# PCB-111000_V2.net
KiCad netlist of a schematic drawn in EAGLE
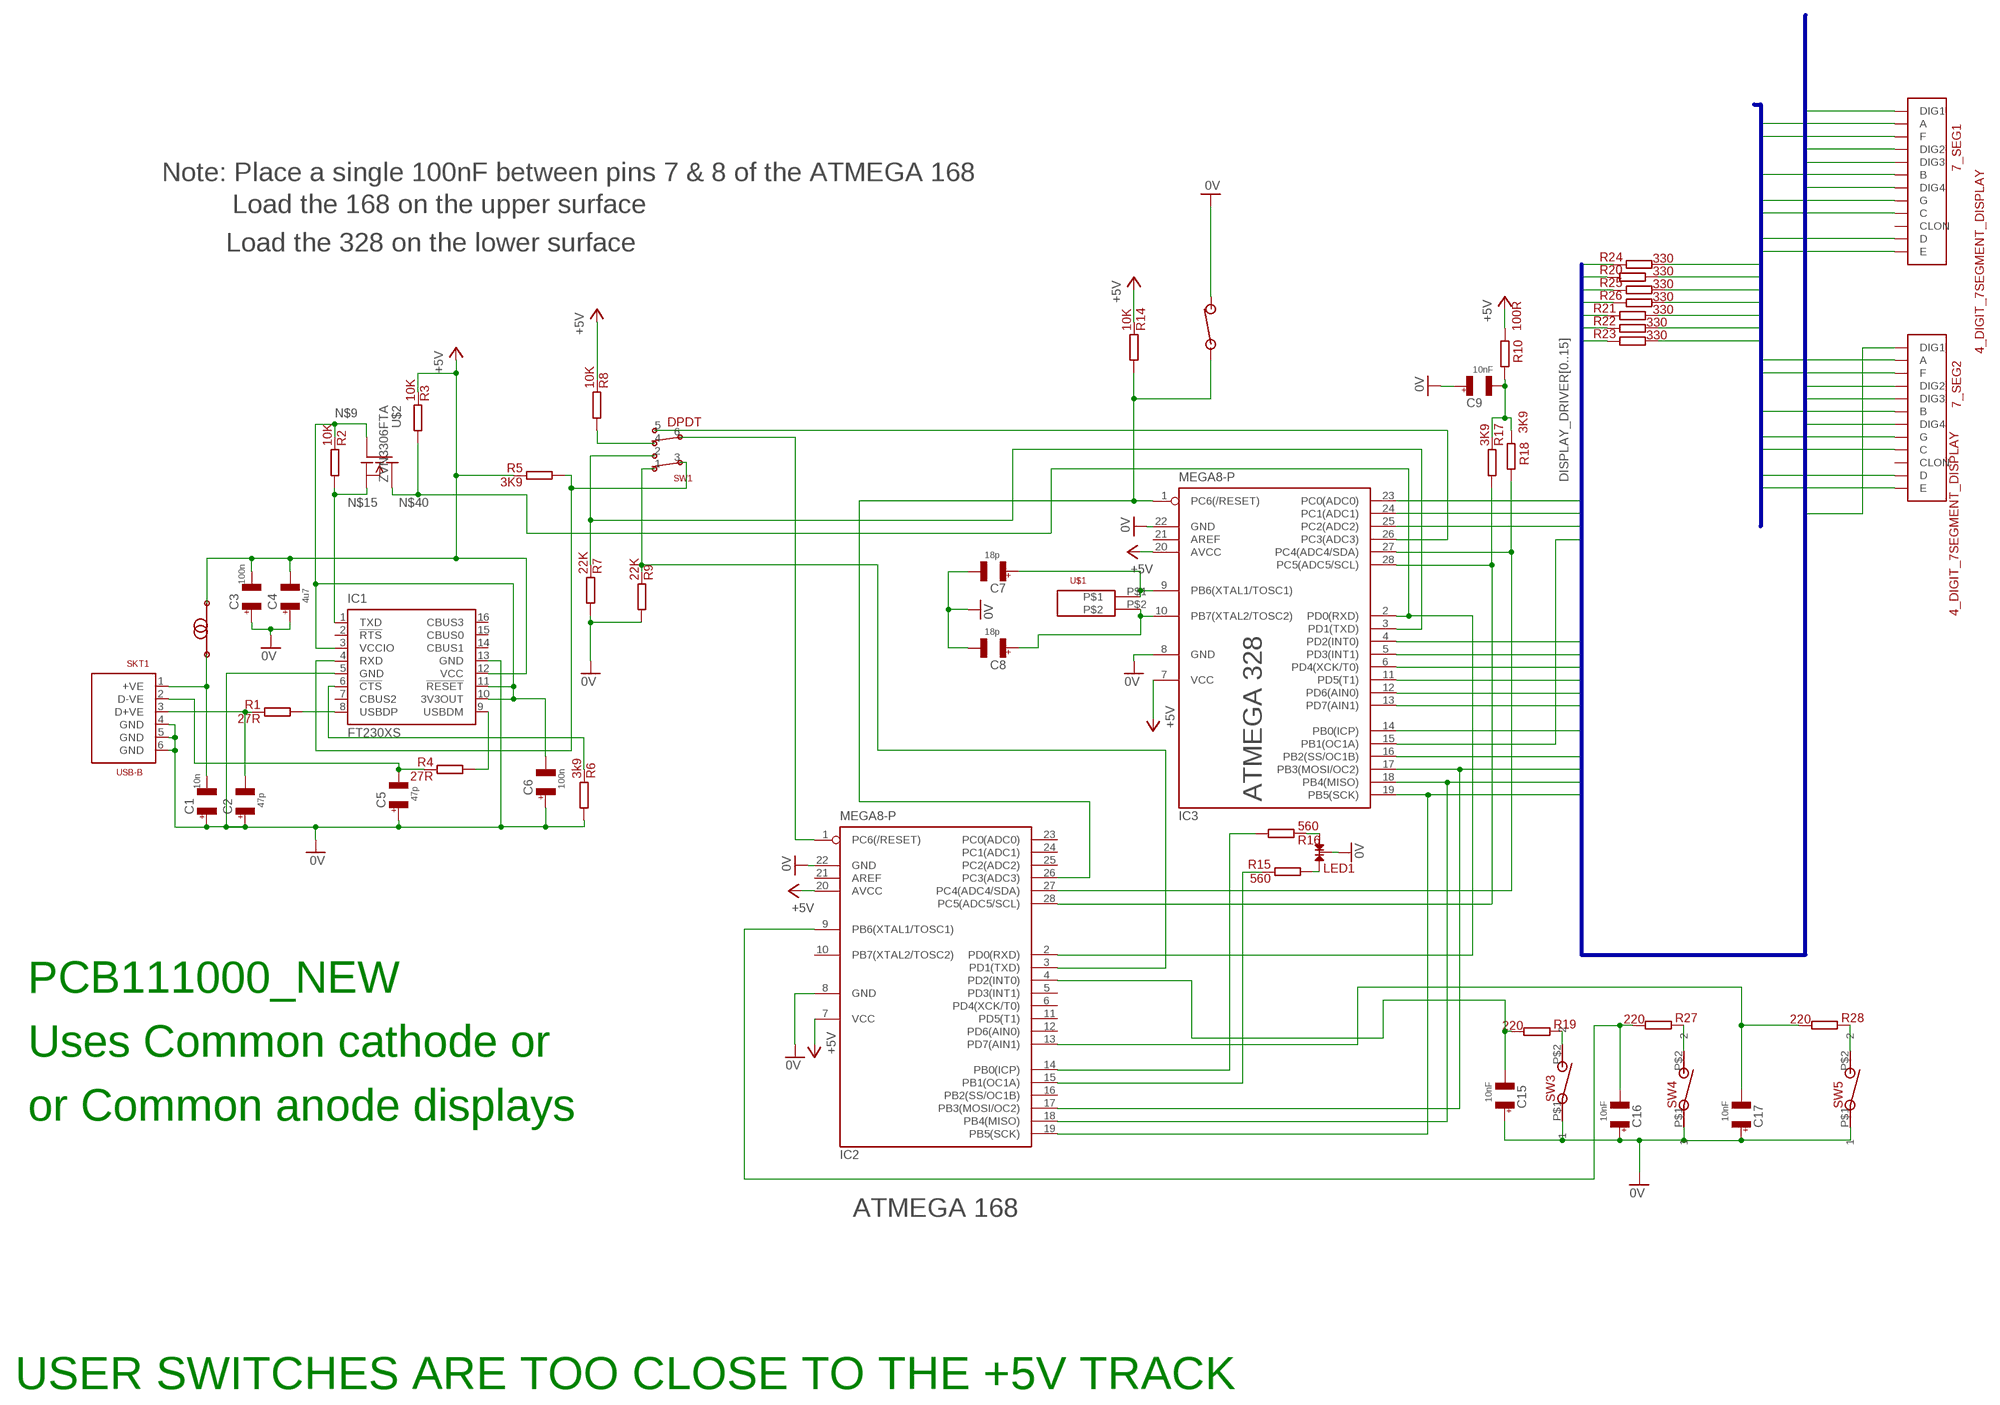
[diagram p0: schematic, sheet 1]

(export (version "E")
  (design (tool "Eeschema 10.0.6"))
  (components
    (comp (ref "7_SEG1")
      (value "4_DIGIT_7SEGMENT_DISPLAY")
      (footprint "eagle-import:4_DIGIT_7SEGMENT_DISPLAY")
      (libsource (lib "eagle-import") (part "4_DIGIT_7SEGMENT_DISPLAY"))
    )
    (comp (ref "7_SEG2")
      (value "4_DIGIT_7SEGMENT_DISPLAY")
      (footprint "eagle-import:4_DIGIT_7SEGMENT_DISPLAY")
      (libsource (lib "eagle-import") (part "4_DIGIT_7SEGMENT_DISPLAY"))
    )
    (comp (ref "C1")
      (value "10n")
      (footprint "eagle-import:1206")
      (libsource (lib "eagle-import") (part "1206C"))
    )
    (comp (ref "C2")
      (value "47p")
      (footprint "eagle-import:1206")
      (libsource (lib "eagle-import") (part "1206C"))
    )
    (comp (ref "C3")
      (value "100n")
      (footprint "eagle-import:1206")
      (libsource (lib "eagle-import") (part "1206C"))
    )
    (comp (ref "C4")
      (value "4u7")
      (footprint "eagle-import:1206")
      (libsource (lib "eagle-import") (part "1206C"))
    )
    (comp (ref "C5")
      (value "47p")
      (footprint "eagle-import:1206")
      (libsource (lib "eagle-import") (part "1206C"))
    )
    (comp (ref "C6")
      (value "100n")
      (footprint "eagle-import:1206")
      (libsource (lib "eagle-import") (part "1206C"))
    )
    (comp (ref "C7")
      (value "18p")
      (footprint "eagle-import:0805")
      (libsource (lib "eagle-import") (part "0805C"))
    )
    (comp (ref "C8")
      (value "18p")
      (footprint "eagle-import:0805")
      (libsource (lib "eagle-import") (part "0805C"))
    )
    (comp (ref "C9")
      (value "10nF")
      (footprint "eagle-import:1206")
      (libsource (lib "eagle-import") (part "1206C"))
    )
    (comp (ref "C15")
      (value "10nF")
      (footprint "eagle-import:1206")
      (libsource (lib "eagle-import") (part "1206C"))
    )
    (comp (ref "C16")
      (value "10nF")
      (footprint "eagle-import:1206")
      (libsource (lib "eagle-import") (part "1206C"))
    )
    (comp (ref "C17")
      (value "10nF")
      (footprint "eagle-import:1206")
      (libsource (lib "eagle-import") (part "1206C"))
    )
    (comp (ref "IC1")
      (value "FT230XS")
      (footprint "eagle-import:SSOP16")
      (libsource (lib "eagle-import") (part "FT230XS"))
    )
    (comp (ref "IC2")
      (value "MEGA8-P")
      (footprint "eagle-import:DIL28-3")
      (libsource (lib "eagle-import") (part "MEGA8-P"))
    )
    (comp (ref "IC3")
      (value "MEGA8-P")
      (footprint "eagle-import:DIL28-3")
      (libsource (lib "eagle-import") (part "MEGA8-P"))
    )
    (comp (ref "L1")
      (value "CHOKE")
      (footprint "eagle-import:1206")
      (libsource (lib "eagle-import") (part "CHOKE"))
    )
    (comp (ref "LED1")
      (value "LED")
      (footprint "eagle-import:CA_DUAL_LED")
      (libsource (lib "eagle-import") (part "LED"))
    )
    (comp (ref "R1")
      (value "27R")
      (footprint "eagle-import:1206")
      (libsource (lib "eagle-import") (part "1206R"))
    )
    (comp (ref "R2")
      (value "10K")
      (footprint "eagle-import:1206")
      (libsource (lib "eagle-import") (part "1206R"))
    )
    (comp (ref "R3")
      (value "10K")
      (footprint "eagle-import:1206")
      (libsource (lib "eagle-import") (part "1206R"))
    )
    (comp (ref "R4")
      (value "27R")
      (footprint "eagle-import:1206")
      (libsource (lib "eagle-import") (part "1206R"))
    )
    (comp (ref "R5")
      (value "3K9")
      (footprint "eagle-import:1206")
      (libsource (lib "eagle-import") (part "1206R"))
    )
    (comp (ref "R6")
      (value "3k9")
      (footprint "eagle-import:1206")
      (libsource (lib "eagle-import") (part "1206R"))
    )
    (comp (ref "R7")
      (value "22K")
      (footprint "eagle-import:1206")
      (libsource (lib "eagle-import") (part "1206R"))
    )
    (comp (ref "R8")
      (value "10K")
      (footprint "eagle-import:1206")
      (libsource (lib "eagle-import") (part "1206R"))
    )
    (comp (ref "R9")
      (value "22K")
      (footprint "eagle-import:1206")
      (libsource (lib "eagle-import") (part "1206R"))
    )
    (comp (ref "R10")
      (value "100R")
      (footprint "eagle-import:1206")
      (libsource (lib "eagle-import") (part "1206R"))
    )
    (comp (ref "R14")
      (value "10K")
      (footprint "eagle-import:1206")
      (libsource (lib "eagle-import") (part "1206R"))
    )
    (comp (ref "R15")
      (value "560")
      (footprint "eagle-import:1206")
      (libsource (lib "eagle-import") (part "1206R"))
    )
    (comp (ref "R16")
      (value "560")
      (footprint "eagle-import:1206")
      (libsource (lib "eagle-import") (part "1206R"))
    )
    (comp (ref "R17")
      (value "3K9")
      (footprint "eagle-import:1206")
      (libsource (lib "eagle-import") (part "1206R"))
    )
    (comp (ref "R18")
      (value "3K9")
      (footprint "eagle-import:1206")
      (libsource (lib "eagle-import") (part "1206R"))
    )
    (comp (ref "R19")
      (value "220")
      (footprint "eagle-import:1206")
      (libsource (lib "eagle-import") (part "1206R"))
    )
    (comp (ref "R20")
      (value "330")
      (footprint "eagle-import:1206")
      (libsource (lib "eagle-import") (part "1206R"))
    )
    (comp (ref "R21")
      (value "330")
      (footprint "eagle-import:1206")
      (libsource (lib "eagle-import") (part "1206R"))
    )
    (comp (ref "R22")
      (value "330")
      (footprint "eagle-import:1206")
      (libsource (lib "eagle-import") (part "1206R"))
    )
    (comp (ref "R23")
      (value "330")
      (footprint "eagle-import:1206")
      (libsource (lib "eagle-import") (part "1206R"))
    )
    (comp (ref "R24")
      (value "330")
      (footprint "eagle-import:1206")
      (libsource (lib "eagle-import") (part "1206R"))
    )
    (comp (ref "R25")
      (value "330")
      (footprint "eagle-import:1206")
      (libsource (lib "eagle-import") (part "1206R"))
    )
    (comp (ref "R26")
      (value "330")
      (footprint "eagle-import:1206")
      (libsource (lib "eagle-import") (part "1206R"))
    )
    (comp (ref "R27")
      (value "220")
      (footprint "eagle-import:1206")
      (libsource (lib "eagle-import") (part "1206R"))
    )
    (comp (ref "R28")
      (value "220")
      (footprint "eagle-import:1206")
      (libsource (lib "eagle-import") (part "1206R"))
    )
    (comp (ref "SKT1")
      (value "USB-B")
      (footprint "eagle-import:USB-B")
      (libsource (lib "eagle-import") (part "USB-B"))
    )
    (comp (ref "SW1")
      (value "DPDT")
      (footprint "eagle-import:DPDT_SWITCH")
      (libsource (lib "eagle-import") (part "DPDT"))
    )
    (comp (ref "SW2")
      (value "NO_SW")
      (footprint "eagle-import:SM_NO_PUSH_BUTTON")
      (libsource (lib "eagle-import") (part "NO_SW"))
    )
    (comp (ref "SW3")
      (value "NO_PB_1")
      (footprint "eagle-import:RE51-0711")
      (libsource (lib "eagle-import") (part "NO_PB_1"))
    )
    (comp (ref "SW4")
      (value "NO_PB_1")
      (footprint "eagle-import:RE51-0711")
      (libsource (lib "eagle-import") (part "NO_PB_1"))
    )
    (comp (ref "SW5")
      (value "NO_PB_1")
      (footprint "eagle-import:RE51-0711")
      (libsource (lib "eagle-import") (part "NO_PB_1"))
    )
    (comp (ref "U$1")
      (value "XTAL")
      (footprint "eagle-import:XTAL_VIAS")
      (libsource (lib "eagle-import") (part "XTAL"))
    )
    (comp (ref "U$2")
      (value "ZVN3306FTA")
      (footprint "eagle-import:SOT-23")
      (libsource (lib "eagle-import") (part "ZVN3306FTA"))
    )
  )
  (nets
    (net (code "2") (name "+5V") (class "Default")
      (node (ref "C3") (pin "P$2") (pinfunction "2_P$2") (pintype "bidirectional"))
      (node (ref "C4") (pin "P$2") (pinfunction "2_P$2") (pintype "bidirectional"))
      (node (ref "IC1") (pin "12") (pinfunction "VCC_12") (pintype "power_in"))
      (node (ref "IC2") (pin "20") (pinfunction "AVCC_20") (pintype "power_in"))
      (node (ref "IC2") (pin "7") (pinfunction "VCC_7") (pintype "power_in"))
      (node (ref "IC3") (pin "20") (pinfunction "AVCC_20") (pintype "power_in"))
      (node (ref "IC3") (pin "7") (pinfunction "VCC_7") (pintype "power_in"))
      (node (ref "L1") (pin "P$2") (pinfunction "2_P$2") (pintype "bidirectional"))
      (node (ref "R10") (pin "P$2") (pinfunction "P$2_P$2") (pintype "bidirectional"))
      (node (ref "R14") (pin "P$2") (pinfunction "P$2_P$2") (pintype "bidirectional"))
      (node (ref "R3") (pin "P$2") (pinfunction "P$2_P$2") (pintype "bidirectional"))
      (node (ref "R5") (pin "P$2") (pinfunction "P$2_P$2") (pintype "bidirectional"))
      (node (ref "R8") (pin "P$2") (pinfunction "P$2_P$2") (pintype "bidirectional"))
    )
    (net (code "3") (name "/DISPLAY_DRIVER0") (class "Default")
      (node (ref "IC3") (pin "15") (pinfunction "PB1(OC1A)_15") (pintype "bidirectional"))
      (node (ref "R24") (pin "P$2") (pinfunction "P$2_P$2") (pintype "bidirectional"))
    )
    (net (code "4") (name "/DISPLAY_DRIVER1") (class "Default")
      (node (ref "IC3") (pin "4") (pinfunction "PD2(INT0)_4") (pintype "bidirectional"))
      (node (ref "R20") (pin "P$2") (pinfunction "P$2_P$2") (pintype "bidirectional"))
    )
    (net (code "5") (name "/DISPLAY_DRIVER2") (class "Default")
      (node (ref "IC3") (pin "5") (pinfunction "PD3(INT1)_5") (pintype "bidirectional"))
      (node (ref "R25") (pin "P$2") (pinfunction "P$2_P$2") (pintype "bidirectional"))
    )
    (net (code "6") (name "/DISPLAY_DRIVER3") (class "Default")
      (node (ref "IC3") (pin "6") (pinfunction "PD4(XCK/T0)_6") (pintype "bidirectional"))
      (node (ref "R26") (pin "P$2") (pinfunction "P$2_P$2") (pintype "bidirectional"))
    )
    (net (code "7") (name "/DISPLAY_DRIVER4") (class "Default")
      (node (ref "IC3") (pin "11") (pinfunction "PD5(T1)_11") (pintype "bidirectional"))
      (node (ref "R21") (pin "P$2") (pinfunction "P$2_P$2") (pintype "bidirectional"))
    )
    (net (code "8") (name "/DISPLAY_DRIVER5") (class "Default")
      (node (ref "IC3") (pin "12") (pinfunction "PD6(AIN0)_12") (pintype "bidirectional"))
      (node (ref "R22") (pin "P$2") (pinfunction "P$2_P$2") (pintype "bidirectional"))
    )
    (net (code "9") (name "/DISPLAY_DRIVER6") (class "Default")
      (node (ref "IC3") (pin "13") (pinfunction "PD7(AIN1)_13") (pintype "bidirectional"))
      (node (ref "R23") (pin "P$2") (pinfunction "P$2_P$2") (pintype "bidirectional"))
    )
    (net (code "10") (name "/DISPLAY_DRIVER8") (class "Default")
      (node (ref "7_SEG2") (pin "P$12") (pinfunction "DIG1_P$12") (pintype "bidirectional"))
      (node (ref "IC3") (pin "14") (pinfunction "PB0(ICP)_14") (pintype "bidirectional"))
    )
    (net (code "11") (name "/DISPLAY_DRIVER9") (class "Default")
      (node (ref "7_SEG2") (pin "P$9") (pinfunction "DIG2_P$9") (pintype "bidirectional"))
      (node (ref "IC3") (pin "16") (pinfunction "PB2(SS/OC1B)_16") (pintype "bidirectional"))
    )
    (net (code "12") (name "/DISPLAY_DRIVER10") (class "Default")
      (node (ref "7_SEG2") (pin "P$8") (pinfunction "DIG3_P$8") (pintype "bidirectional"))
      (node (ref "IC2") (pin "17") (pinfunction "PB3(MOSI/OC2)_17") (pintype "bidirectional"))
      (node (ref "IC3") (pin "17") (pinfunction "PB3(MOSI/OC2)_17") (pintype "bidirectional"))
    )
    (net (code "13") (name "/DISPLAY_DRIVER11") (class "Default")
      (node (ref "7_SEG2") (pin "P$6") (pinfunction "DIG4_P$6") (pintype "bidirectional"))
      (node (ref "IC2") (pin "18") (pinfunction "PB4(MISO)_18") (pintype "bidirectional"))
      (node (ref "IC3") (pin "18") (pinfunction "PB4(MISO)_18") (pintype "bidirectional"))
    )
    (net (code "14") (name "/DISPLAY_DRIVER12") (class "Default")
      (node (ref "7_SEG1") (pin "P$12") (pinfunction "DIG1_P$12") (pintype "bidirectional"))
      (node (ref "IC2") (pin "19") (pinfunction "PB5(SCK)_19") (pintype "bidirectional"))
      (node (ref "IC3") (pin "19") (pinfunction "PB5(SCK)_19") (pintype "bidirectional"))
    )
    (net (code "15") (name "/DISPLAY_DRIVER13") (class "Default")
      (node (ref "7_SEG1") (pin "P$9") (pinfunction "DIG2_P$9") (pintype "bidirectional"))
      (node (ref "IC3") (pin "23") (pinfunction "PC0(ADC0)_23") (pintype "bidirectional"))
    )
    (net (code "16") (name "/DISPLAY_DRIVER14") (class "Default")
      (node (ref "7_SEG1") (pin "P$8") (pinfunction "DIG3_P$8") (pintype "bidirectional"))
      (node (ref "IC3") (pin "24") (pinfunction "PC1(ADC1)_24") (pintype "bidirectional"))
    )
    (net (code "17") (name "/DISPLAY_DRIVER15") (class "Default")
      (node (ref "7_SEG1") (pin "P$6") (pinfunction "DIG4_P$6") (pintype "bidirectional"))
      (node (ref "IC3") (pin "25") (pinfunction "PC2(ADC2)_25") (pintype "bidirectional"))
    )
    (net (code "19") (name "/N$9") (class "Default")
      (node (ref "C6") (pin "P$2") (pinfunction "2_P$2") (pintype "bidirectional"))
      (node (ref "IC1") (pin "10") (pinfunction "3V3OUT_10") (pintype "output"))
      (node (ref "IC1") (pin "11") (pinfunction "~{RESET}_11") (pintype "input"))
      (node (ref "IC1") (pin "3") (pinfunction "VCCIO_3") (pintype "power_in"))
      (node (ref "R2") (pin "P$2") (pinfunction "P$2_P$2") (pintype "bidirectional"))
      (node (ref "U$2") (pin "3") (pinfunction "G_3") (pintype "passive"))
    )
    (net (code "20") (name "/N$15") (class "Default")
      (node (ref "IC1") (pin "1") (pinfunction "TXD_1") (pintype "output"))
      (node (ref "R2") (pin "P$1") (pinfunction "P$1_P$1") (pintype "bidirectional"))
      (node (ref "U$2") (pin "2") (pinfunction "S_2") (pintype "passive"))
    )
    (net (code "21") (name "/N$40") (class "Default")
      (node (ref "IC2") (pin "2") (pinfunction "PD0(RXD)_2") (pintype "bidirectional"))
      (node (ref "IC3") (pin "2") (pinfunction "PD0(RXD)_2") (pintype "bidirectional"))
      (node (ref "R3") (pin "P$1") (pinfunction "P$1_P$1") (pintype "bidirectional"))
      (node (ref "U$2") (pin "1") (pinfunction "D_1") (pintype "passive"))
    )
    (net (code "22") (name "/SEVEN_SEG0") (class "Default")
      (node (ref "7_SEG1") (pin "P$11") (pinfunction "A_P$11") (pintype "bidirectional"))
      (node (ref "7_SEG2") (pin "P$11") (pinfunction "A_P$11") (pintype "bidirectional"))
      (node (ref "R24") (pin "P$1") (pinfunction "P$1_P$1") (pintype "bidirectional"))
    )
    (net (code "23") (name "/SEVEN_SEG1") (class "Default")
      (node (ref "7_SEG1") (pin "P$7") (pinfunction "B_P$7") (pintype "bidirectional"))
      (node (ref "7_SEG2") (pin "P$7") (pinfunction "B_P$7") (pintype "bidirectional"))
      (node (ref "R20") (pin "P$1") (pinfunction "P$1_P$1") (pintype "bidirectional"))
    )
    (net (code "24") (name "/SEVEN_SEG2") (class "Default")
      (node (ref "7_SEG1") (pin "P$4") (pinfunction "C_P$4") (pintype "bidirectional"))
      (node (ref "7_SEG2") (pin "P$4") (pinfunction "C_P$4") (pintype "bidirectional"))
      (node (ref "R25") (pin "P$1") (pinfunction "P$1_P$1") (pintype "bidirectional"))
    )
    (net (code "25") (name "/SEVEN_SEG3") (class "Default")
      (node (ref "7_SEG1") (pin "P$2") (pinfunction "D_P$2") (pintype "bidirectional"))
      (node (ref "7_SEG2") (pin "P$2") (pinfunction "D_P$2") (pintype "bidirectional"))
      (node (ref "R26") (pin "P$1") (pinfunction "P$1_P$1") (pintype "bidirectional"))
    )
    (net (code "26") (name "/SEVEN_SEG4") (class "Default")
      (node (ref "7_SEG1") (pin "P$1") (pinfunction "E_P$1") (pintype "bidirectional"))
      (node (ref "7_SEG2") (pin "P$1") (pinfunction "E_P$1") (pintype "bidirectional"))
      (node (ref "R21") (pin "P$1") (pinfunction "P$1_P$1") (pintype "bidirectional"))
    )
    (net (code "27") (name "/SEVEN_SEG5") (class "Default")
      (node (ref "7_SEG1") (pin "P$10") (pinfunction "F_P$10") (pintype "bidirectional"))
      (node (ref "7_SEG2") (pin "P$10") (pinfunction "F_P$10") (pintype "bidirectional"))
      (node (ref "R22") (pin "P$1") (pinfunction "P$1_P$1") (pintype "bidirectional"))
    )
    (net (code "28") (name "/SEVEN_SEG6") (class "Default")
      (node (ref "7_SEG1") (pin "P$5") (pinfunction "G_P$5") (pintype "bidirectional"))
      (node (ref "7_SEG2") (pin "P$5") (pinfunction "G_P$5") (pintype "bidirectional"))
      (node (ref "R23") (pin "P$1") (pinfunction "P$1_P$1") (pintype "bidirectional"))
    )
    (net (code "29") (name "0V") (class "Default")
      (node (ref "C1") (pin "P$1") (pinfunction "1_P$1") (pintype "bidirectional"))
      (node (ref "C15") (pin "P$1") (pinfunction "1_P$1") (pintype "bidirectional"))
      (node (ref "C16") (pin "P$1") (pinfunction "1_P$1") (pintype "bidirectional"))
      (node (ref "C17") (pin "P$1") (pinfunction "1_P$1") (pintype "bidirectional"))
      (node (ref "C2") (pin "P$1") (pinfunction "1_P$1") (pintype "bidirectional"))
      (node (ref "C3") (pin "P$1") (pinfunction "1_P$1") (pintype "bidirectional"))
      (node (ref "C4") (pin "P$1") (pinfunction "1_P$1") (pintype "bidirectional"))
      (node (ref "C5") (pin "P$1") (pinfunction "1_P$1") (pintype "bidirectional"))
      (node (ref "C6") (pin "P$1") (pinfunction "1_P$1") (pintype "bidirectional"))
      (node (ref "C7") (pin "2") (pinfunction "2_2") (pintype "bidirectional"))
      (node (ref "C8") (pin "2") (pinfunction "2_2") (pintype "bidirectional"))
      (node (ref "C9") (pin "P$1") (pinfunction "1_P$1") (pintype "bidirectional"))
      (node (ref "IC1") (pin "13") (pinfunction "GND_13") (pintype "power_in"))
      (node (ref "IC1") (pin "5") (pinfunction "GND_5") (pintype "power_in"))
      (node (ref "IC2") (pin "22") (pinfunction "GND_22") (pintype "power_in"))
      (node (ref "IC2") (pin "8") (pinfunction "GND_8") (pintype "power_in"))
      (node (ref "IC3") (pin "22") (pinfunction "GND_22") (pintype "power_in"))
      (node (ref "IC3") (pin "8") (pinfunction "GND_8") (pintype "power_in"))
      (node (ref "LED1") (pin "2") (pinfunction "2_2") (pintype "bidirectional"))
      (node (ref "R6") (pin "P$1") (pinfunction "P$1_P$1") (pintype "bidirectional"))
      (node (ref "R7") (pin "P$1") (pinfunction "P$1_P$1") (pintype "bidirectional"))
      (node (ref "R9") (pin "P$1") (pinfunction "P$1_P$1") (pintype "bidirectional"))
      (node (ref "SKT1") (pin "4") (pinfunction "GND_4") (pintype "bidirectional"))
      (node (ref "SKT1") (pin "5") (pinfunction "GND_5") (pintype "bidirectional"))
      (node (ref "SKT1") (pin "6") (pinfunction "GND_6") (pintype "bidirectional"))
      (node (ref "SW2") (pin "P$2") (pinfunction "2_P$2") (pintype "bidirectional"))
      (node (ref "SW3") (pin "P$1") (pinfunction "1_P$1") (pintype "bidirectional"))
      (node (ref "SW4") (pin "P$1") (pinfunction "1_P$1") (pintype "bidirectional"))
      (node (ref "SW5") (pin "P$1") (pinfunction "1_P$1") (pintype "bidirectional"))
    )
    (net (code "30") (name "Net-(C1-2)") (class "Default")
      (node (ref "C1") (pin "P$2") (pinfunction "2_P$2") (pintype "bidirectional"))
      (node (ref "L1") (pin "P$1") (pinfunction "1_P$1") (pintype "bidirectional"))
      (node (ref "SKT1") (pin "1") (pinfunction "+VE_1") (pintype "bidirectional"))
    )
    (net (code "31") (name "Net-(C2-2)") (class "Default")
      (node (ref "C2") (pin "P$2") (pinfunction "2_P$2") (pintype "bidirectional"))
      (node (ref "R1") (pin "P$2") (pinfunction "P$2_P$2") (pintype "bidirectional"))
      (node (ref "SKT1") (pin "3") (pinfunction "D+VE_3") (pintype "bidirectional"))
    )
    (net (code "32") (name "Net-(C5-2)") (class "Default")
      (node (ref "C5") (pin "P$2") (pinfunction "2_P$2") (pintype "bidirectional"))
      (node (ref "R4") (pin "P$2") (pinfunction "P$2_P$2") (pintype "bidirectional"))
      (node (ref "SKT1") (pin "2") (pinfunction "D-VE_2") (pintype "bidirectional"))
    )
    (net (code "33") (name "Net-(C9-2)") (class "Default")
      (node (ref "C9") (pin "P$2") (pinfunction "2_P$2") (pintype "bidirectional"))
      (node (ref "R10") (pin "P$1") (pinfunction "P$1_P$1") (pintype "bidirectional"))
      (node (ref "R17") (pin "P$2") (pinfunction "P$2_P$2") (pintype "bidirectional"))
      (node (ref "R18") (pin "P$2") (pinfunction "P$2_P$2") (pintype "bidirectional"))
    )
    (net (code "34") (name "Net-(C15-2)") (class "Default")
      (node (ref "C15") (pin "P$2") (pinfunction "2_P$2") (pintype "bidirectional"))
      (node (ref "IC2") (pin "4") (pinfunction "PD2(INT0)_4") (pintype "bidirectional"))
      (node (ref "R19") (pin "P$1") (pinfunction "P$1_P$1") (pintype "bidirectional"))
    )
    (net (code "35") (name "Net-(C16-2)") (class "Default")
      (node (ref "C16") (pin "P$2") (pinfunction "2_P$2") (pintype "bidirectional"))
      (node (ref "IC2") (pin "9") (pinfunction "PB6(XTAL1/TOSC1)_9") (pintype "bidirectional"))
      (node (ref "R27") (pin "P$1") (pinfunction "P$1_P$1") (pintype "bidirectional"))
    )
    (net (code "36") (name "Net-(C17-2)") (class "Default")
      (node (ref "C17") (pin "P$2") (pinfunction "2_P$2") (pintype "bidirectional"))
      (node (ref "IC2") (pin "13") (pinfunction "PD7(AIN1)_13") (pintype "bidirectional"))
      (node (ref "R28") (pin "P$1") (pinfunction "P$1_P$1") (pintype "bidirectional"))
    )
    (net (code "37") (name "Net-(IC1-RXD)") (class "Default")
      (node (ref "IC1") (pin "4") (pinfunction "RXD_4") (pintype "input"))
      (node (ref "R5") (pin "P$1") (pinfunction "P$1_P$1") (pintype "bidirectional"))
      (node (ref "SW1") (pin "3") (pinfunction "3_3") (pintype "bidirectional"))
    )
    (net (code "38") (name "Net-(IC1-USBDM)") (class "Default")
      (node (ref "IC1") (pin "9") (pinfunction "USBDM_9") (pintype "input"))
      (node (ref "R4") (pin "P$1") (pinfunction "P$1_P$1") (pintype "bidirectional"))
    )
    (net (code "39") (name "Net-(IC1-USBDP)") (class "Default")
      (node (ref "IC1") (pin "8") (pinfunction "USBDP_8") (pintype "input"))
      (node (ref "R1") (pin "P$1") (pinfunction "P$1_P$1") (pintype "bidirectional"))
    )
    (net (code "40") (name "Net-(IC1-~{CTS})") (class "Default")
      (node (ref "IC1") (pin "6") (pinfunction "~{CTS}_6") (pintype "input"))
      (node (ref "R6") (pin "P$2") (pinfunction "P$2_P$2") (pintype "bidirectional"))
    )
    (net (code "41") (name "Net-(IC2-PB0(ICP))") (class "Default")
      (node (ref "IC2") (pin "14") (pinfunction "PB0(ICP)_14") (pintype "bidirectional"))
      (node (ref "R16") (pin "P$1") (pinfunction "P$1_P$1") (pintype "bidirectional"))
    )
    (net (code "42") (name "Net-(IC2-PB1(OC1A))") (class "Default")
      (node (ref "IC2") (pin "15") (pinfunction "PB1(OC1A)_15") (pintype "bidirectional"))
      (node (ref "R15") (pin "P$2") (pinfunction "P$2_P$2") (pintype "bidirectional"))
    )
    (net (code "43") (name "Net-(IC2-PC3(ADC3))") (class "Default")
      (node (ref "IC2") (pin "26") (pinfunction "PC3(ADC3)_26") (pintype "bidirectional"))
      (node (ref "IC3") (pin "1") (pinfunction "PC6(/RESET)_1") (pintype "bidirectional"))
      (node (ref "R14") (pin "P$1") (pinfunction "P$1_P$1") (pintype "bidirectional"))
      (node (ref "SW2") (pin "P$1") (pinfunction "1_P$1") (pintype "bidirectional"))
    )
    (net (code "44") (name "Net-(IC2-PC4(ADC4{slash}SDA))") (class "Default")
      (node (ref "IC2") (pin "27") (pinfunction "PC4(ADC4/SDA)_27") (pintype "bidirectional"))
      (node (ref "IC3") (pin "27") (pinfunction "PC4(ADC4/SDA)_27") (pintype "bidirectional"))
      (node (ref "R18") (pin "P$1") (pinfunction "P$1_P$1") (pintype "bidirectional"))
    )
    (net (code "45") (name "Net-(IC2-PC5(ADC5{slash}SCL))") (class "Default")
      (node (ref "IC2") (pin "28") (pinfunction "PC5(ADC5/SCL)_28") (pintype "bidirectional"))
      (node (ref "IC3") (pin "28") (pinfunction "PC5(ADC5/SCL)_28") (pintype "bidirectional"))
      (node (ref "R17") (pin "P$1") (pinfunction "P$1_P$1") (pintype "bidirectional"))
    )
    (net (code "46") (name "Net-(IC2-PC6({slash}RESET))") (class "Default")
      (node (ref "IC2") (pin "1") (pinfunction "PC6(/RESET)_1") (pintype "bidirectional"))
      (node (ref "SW1") (pin "6") (pinfunction "6_6") (pintype "bidirectional"))
    )
    (net (code "47") (name "Net-(IC2-PD1(TXD))") (class "Default")
      (node (ref "IC2") (pin "3") (pinfunction "PD1(TXD)_3") (pintype "bidirectional"))
      (node (ref "R9") (pin "P$2") (pinfunction "P$2_P$2") (pintype "bidirectional"))
      (node (ref "SW1") (pin "1") (pinfunction "1_1") (pintype "bidirectional"))
    )
    (net (code "48") (name "Net-(IC3-PB6(XTAL1{slash}TOSC1))") (class "Default")
      (node (ref "C7") (pin "1") (pinfunction "1_1") (pintype "bidirectional"))
      (node (ref "IC3") (pin "9") (pinfunction "PB6(XTAL1/TOSC1)_9") (pintype "bidirectional"))
      (node (ref "U$1") (pin "P$1") (pinfunction "P$1_P$1") (pintype "bidirectional"))
    )
    (net (code "49") (name "Net-(IC3-PB7(XTAL2{slash}TOSC2))") (class "Default")
      (node (ref "C8") (pin "1") (pinfunction "1_1") (pintype "bidirectional"))
      (node (ref "IC3") (pin "10") (pinfunction "PB7(XTAL2/TOSC2)_10") (pintype "bidirectional"))
      (node (ref "U$1") (pin "P$2") (pinfunction "P$2_P$2") (pintype "bidirectional"))
    )
    (net (code "50") (name "Net-(IC3-PC3(ADC3))") (class "Default")
      (node (ref "IC3") (pin "26") (pinfunction "PC3(ADC3)_26") (pintype "bidirectional"))
      (node (ref "SW1") (pin "5") (pinfunction "5_5") (pintype "bidirectional"))
    )
    (net (code "51") (name "Net-(IC3-PD1(TXD))") (class "Default")
      (node (ref "IC3") (pin "3") (pinfunction "PD1(TXD)_3") (pintype "bidirectional"))
      (node (ref "R7") (pin "P$2") (pinfunction "P$2_P$2") (pintype "bidirectional"))
      (node (ref "SW1") (pin "2") (pinfunction "2_2") (pintype "bidirectional"))
    )
    (net (code "52") (name "Net-(LED1-Pad1)") (class "Default")
      (node (ref "LED1") (pin "1") (pinfunction "1_1") (pintype "bidirectional"))
      (node (ref "R15") (pin "P$1") (pinfunction "P$1_P$1") (pintype "bidirectional"))
    )
    (net (code "53") (name "Net-(LED1-Pad3)") (class "Default")
      (node (ref "LED1") (pin "3") (pinfunction "3_3") (pintype "bidirectional"))
      (node (ref "R16") (pin "P$2") (pinfunction "P$2_P$2") (pintype "bidirectional"))
    )
    (net (code "54") (name "Net-(R8-PadP$1)") (class "Default")
      (node (ref "R8") (pin "P$1") (pinfunction "P$1_P$1") (pintype "bidirectional"))
      (node (ref "SW1") (pin "4") (pinfunction "4_4") (pintype "bidirectional"))
    )
    (net (code "55") (name "Net-(SW3-2)") (class "Default")
      (node (ref "R19") (pin "P$2") (pinfunction "P$2_P$2") (pintype "bidirectional"))
      (node (ref "SW3") (pin "P$2") (pinfunction "2_P$2") (pintype "bidirectional"))
    )
    (net (code "56") (name "Net-(SW4-2)") (class "Default")
      (node (ref "R27") (pin "P$2") (pinfunction "P$2_P$2") (pintype "bidirectional"))
      (node (ref "SW4") (pin "P$2") (pinfunction "2_P$2") (pintype "bidirectional"))
    )
    (net (code "57") (name "Net-(SW5-2)") (class "Default")
      (node (ref "R28") (pin "P$2") (pinfunction "P$2_P$2") (pintype "bidirectional"))
      (node (ref "SW5") (pin "P$2") (pinfunction "2_P$2") (pintype "bidirectional"))
    )
    (net (code "58") (name "unconnected-(7_SEG1-CLON-PadP$3)") (class "Default")
      (node (ref "7_SEG1") (pin "P$3") (pinfunction "CLON_P$3") (pintype "bidirectional"))
    )
    (net (code "59") (name "unconnected-(7_SEG2-CLON-PadP$3)") (class "Default")
      (node (ref "7_SEG2") (pin "P$3") (pinfunction "CLON_P$3") (pintype "bidirectional"))
    )
    (net (code "60") (name "unconnected-(IC1-CBUS0-Pad15)") (class "Default")
      (node (ref "IC1") (pin "15") (pinfunction "CBUS0_15") (pintype "bidirectional"))
    )
    (net (code "61") (name "unconnected-(IC1-CBUS1-Pad14)") (class "Default")
      (node (ref "IC1") (pin "14") (pinfunction "CBUS1_14") (pintype "bidirectional"))
    )
    (net (code "62") (name "unconnected-(IC1-CBUS2-Pad7)") (class "Default")
      (node (ref "IC1") (pin "7") (pinfunction "CBUS2_7") (pintype "bidirectional"))
    )
    (net (code "63") (name "unconnected-(IC1-CBUS3-Pad16)") (class "Default")
      (node (ref "IC1") (pin "16") (pinfunction "CBUS3_16") (pintype "bidirectional"))
    )
    (net (code "64") (name "unconnected-(IC1-~{RTS}-Pad2)") (class "Default")
      (node (ref "IC1") (pin "2") (pinfunction "~{RTS}_2") (pintype "output"))
    )
    (net (code "65") (name "unconnected-(IC2-AREF-Pad21)") (class "Default")
      (node (ref "IC2") (pin "21") (pinfunction "AREF_21") (pintype "passive"))
    )
    (net (code "66") (name "unconnected-(IC2-PB2(SS{slash}OC1B)-Pad16)") (class "Default")
      (node (ref "IC2") (pin "16") (pinfunction "PB2(SS/OC1B)_16") (pintype "bidirectional"))
    )
    (net (code "67") (name "unconnected-(IC2-PB7(XTAL2{slash}TOSC2)-Pad10)") (class "Default")
      (node (ref "IC2") (pin "10") (pinfunction "PB7(XTAL2/TOSC2)_10") (pintype "bidirectional"))
    )
    (net (code "68") (name "unconnected-(IC2-PC0(ADC0)-Pad23)") (class "Default")
      (node (ref "IC2") (pin "23") (pinfunction "PC0(ADC0)_23") (pintype "bidirectional"))
    )
    (net (code "69") (name "unconnected-(IC2-PC1(ADC1)-Pad24)") (class "Default")
      (node (ref "IC2") (pin "24") (pinfunction "PC1(ADC1)_24") (pintype "bidirectional"))
    )
    (net (code "70") (name "unconnected-(IC2-PC2(ADC2)-Pad25)") (class "Default")
      (node (ref "IC2") (pin "25") (pinfunction "PC2(ADC2)_25") (pintype "bidirectional"))
    )
    (net (code "71") (name "unconnected-(IC2-PD3(INT1)-Pad5)") (class "Default")
      (node (ref "IC2") (pin "5") (pinfunction "PD3(INT1)_5") (pintype "bidirectional"))
    )
    (net (code "72") (name "unconnected-(IC2-PD4(XCK{slash}T0)-Pad6)") (class "Default")
      (node (ref "IC2") (pin "6") (pinfunction "PD4(XCK/T0)_6") (pintype "bidirectional"))
    )
    (net (code "73") (name "unconnected-(IC2-PD5(T1)-Pad11)") (class "Default")
      (node (ref "IC2") (pin "11") (pinfunction "PD5(T1)_11") (pintype "bidirectional"))
    )
    (net (code "74") (name "unconnected-(IC2-PD6(AIN0)-Pad12)") (class "Default")
      (node (ref "IC2") (pin "12") (pinfunction "PD6(AIN0)_12") (pintype "bidirectional"))
    )
    (net (code "75") (name "unconnected-(IC3-AREF-Pad21)") (class "Default")
      (node (ref "IC3") (pin "21") (pinfunction "AREF_21") (pintype "passive"))
    )
  )
)
